# SensorCheck.net
KiCad netlist of a schematic drawn in Altium Designer
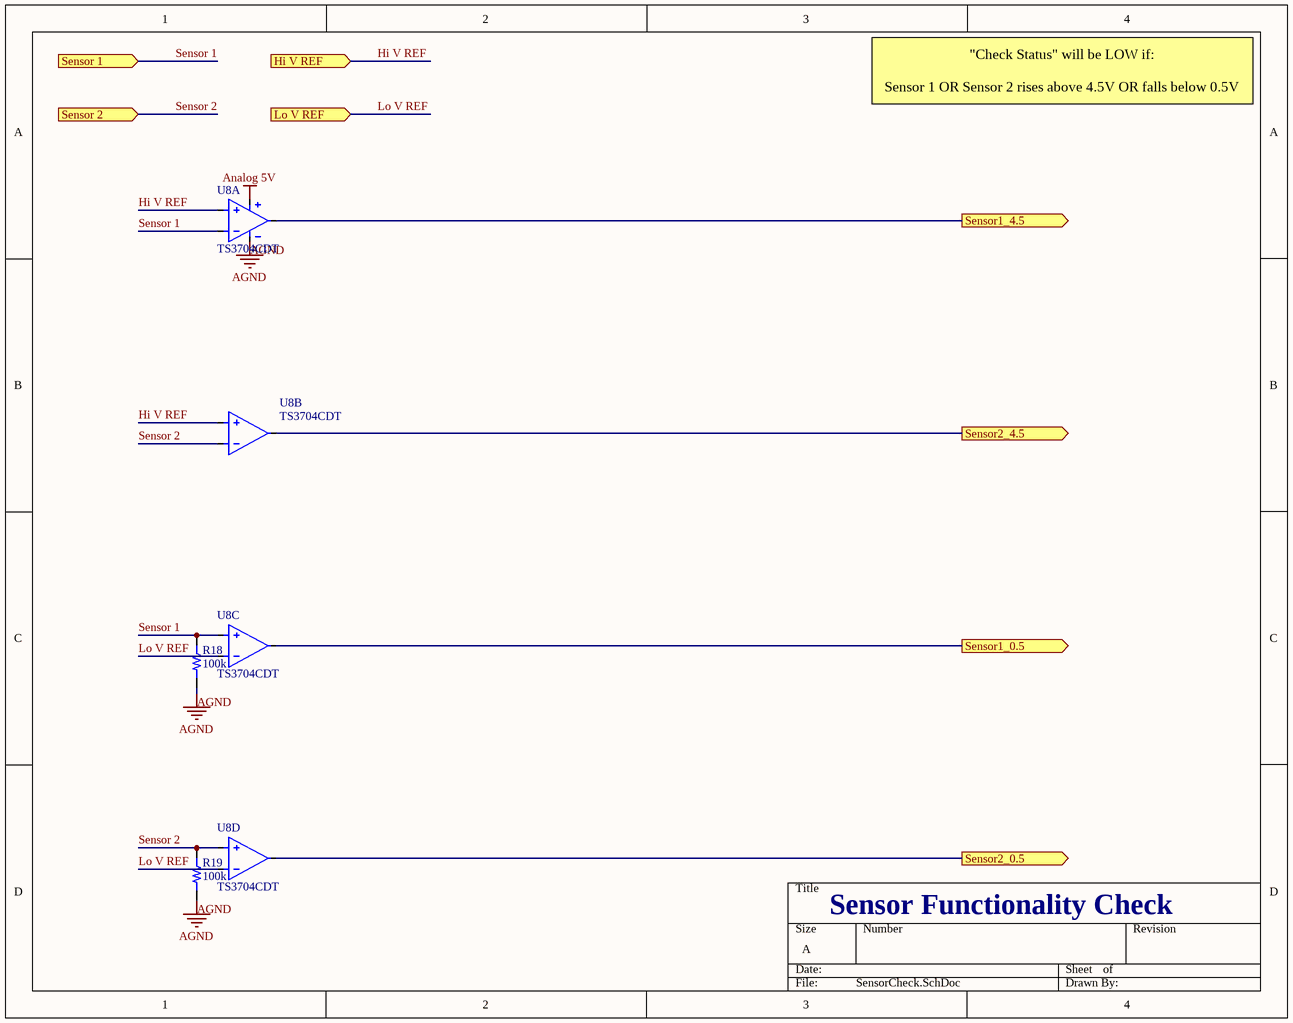
[diagram p0: SensorCheck.SchDoc]

(export (version "E")
  (design (tool "Eeschema 10.0.6"))
  (components
    (comp (ref "R18")
      (value "resistor")
      (footprint "RES 0603/1608")
      (fields (field (name "RESISTANCE") "100k"))
      (libsource (lib "altlib") (part "resistor"))
    )
    (comp (ref "R19")
      (value "resistor")
      (footprint "RES 0603/1608")
      (fields (field (name "RESISTANCE") "100k"))
      (libsource (lib "altlib") (part "resistor"))
    )
    (comp (ref "U8")
      (value "TS3704CDT")
      (footprint "SOIC-14")
      (description "Quad CMOS Comparators")
      (fields (field (name "CREATEDBY") "Kevin"))
      (libsource (lib "altlib") (part "TS3704CDT"))
    )
  )
  (nets
    (net (code "1") (name "/Hi V REF") (class "Default")
      (node (ref "U8") (pin "5") (pinfunction "+IN_1_5") (pintype "passive"))
      (node (ref "U8") (pin "7") (pinfunction "+IN_2_7") (pintype "passive"))
    )
    (net (code "2") (name "/Lo V REF") (class "Default")
      (node (ref "U8") (pin "10") (pinfunction "-IN_4_10") (pintype "passive"))
      (node (ref "U8") (pin "8") (pinfunction "-IN_3_8") (pintype "passive"))
    )
    (net (code "3") (name "/Sensor 1") (class "Default")
      (node (ref "R18") (pin "2") (pinfunction "2_2") (pintype "passive"))
      (node (ref "U8") (pin "4") (pinfunction "-IN_1_4") (pintype "passive"))
      (node (ref "U8") (pin "9") (pinfunction "+IN_3_9") (pintype "passive"))
    )
    (net (code "4") (name "/Sensor 2") (class "Default")
      (node (ref "R19") (pin "2") (pinfunction "2_2") (pintype "passive"))
      (node (ref "U8") (pin "11") (pinfunction "+IN_4_11") (pintype "passive"))
      (node (ref "U8") (pin "6") (pinfunction "-IN_2_6") (pintype "passive"))
    )
    (net (code "5") (name "/Sensor1_0.5") (class "Default")
      (node (ref "U8") (pin "14") (pinfunction "OUT_3_14") (pintype "passive"))
    )
    (net (code "6") (name "/Sensor1_4.5") (class "Default")
      (node (ref "U8") (pin "2") (pinfunction "OUT_1_2") (pintype "passive"))
    )
    (net (code "7") (name "/Sensor2_0.5") (class "Default")
      (node (ref "U8") (pin "13") (pinfunction "OUT_4_13") (pintype "passive"))
    )
    (net (code "8") (name "/Sensor2_4.5") (class "Default")
      (node (ref "U8") (pin "1") (pinfunction "OUT_2_1") (pintype "passive"))
    )
    (net (code "9") (name "AGND") (class "Default")
      (node (ref "R18") (pin "1") (pinfunction "1_1") (pintype "passive"))
      (node (ref "R19") (pin "1") (pinfunction "1_1") (pintype "passive"))
      (node (ref "U8") (pin "12") (pinfunction "V-_12") (pintype "passive"))
    )
    (net (code "10") (name "Analog 5V") (class "Default")
      (node (ref "U8") (pin "3") (pinfunction "V+_3") (pintype "passive"))
    )
  )
)
